# EXT-PHY.net
KiCad netlist of a schematic drawn in EAGLE
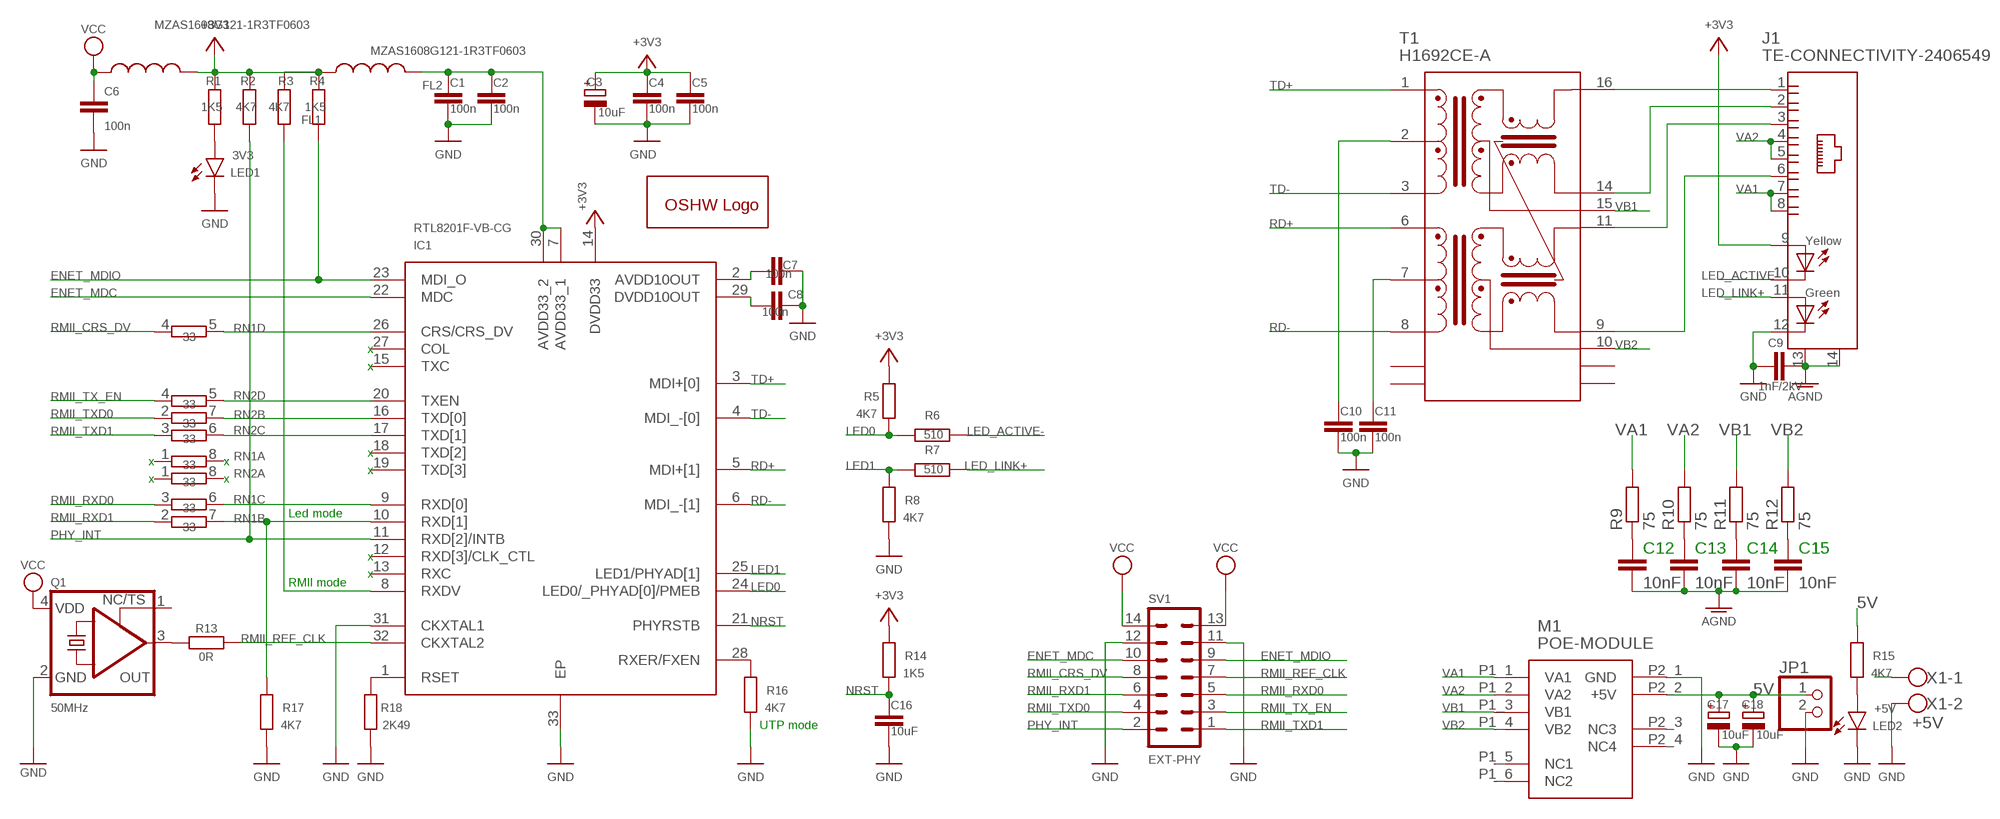
[diagram p0: schematic, sheet 1]

(export (version "E")
  (design (tool "Eeschema 10.0.6"))
  (components
    (comp (ref "C1")
      (value "100n")
      (footprint "eagle-import:C0603")
      (libsource (lib "eagle-import") (part "C-EUC0603"))
    )
    (comp (ref "C2")
      (value "100n")
      (footprint "eagle-import:C0603")
      (libsource (lib "eagle-import") (part "C-EUC0603"))
    )
    (comp (ref "C3")
      (value "10uF")
      (footprint "eagle-import:A_3216-18R")
      (libsource (lib "eagle-import") (part "CPOL-EUA/3216-18R"))
    )
    (comp (ref "C4")
      (value "100n")
      (footprint "eagle-import:C0603")
      (libsource (lib "eagle-import") (part "C-EUC0603"))
    )
    (comp (ref "C5")
      (value "100n")
      (footprint "eagle-import:C0603")
      (libsource (lib "eagle-import") (part "C-EUC0603"))
    )
    (comp (ref "C6")
      (value "100n")
      (footprint "eagle-import:C0603")
      (libsource (lib "eagle-import") (part "C-EUC0603"))
    )
    (comp (ref "C7")
      (value "100n")
      (footprint "eagle-import:C0603")
      (libsource (lib "eagle-import") (part "C-EUC0603"))
    )
    (comp (ref "C8")
      (value "100n")
      (footprint "eagle-import:C0603")
      (libsource (lib "eagle-import") (part "C-EUC0603"))
    )
    (comp (ref "C9")
      (value "1nF/2kV")
      (footprint "eagle-import:C1206")
      (fields (field (name "SPICEPREFIX") "C"))
      (libsource (lib "eagle-import") (part "C-EUC1206"))
    )
    (comp (ref "C10")
      (value "100n")
      (footprint "eagle-import:C0603")
      (libsource (lib "eagle-import") (part "C-EUC0603"))
    )
    (comp (ref "C11")
      (value "100n")
      (footprint "eagle-import:C0603")
      (libsource (lib "eagle-import") (part "C-EUC0603"))
    )
    (comp (ref "C12")
      (value "10nF")
      (footprint "eagle-import:C0805")
      (libsource (lib "eagle-import") (part "C-EUC0805"))
    )
    (comp (ref "C13")
      (value "10nF")
      (footprint "eagle-import:C0805")
      (libsource (lib "eagle-import") (part "C-EUC0805"))
    )
    (comp (ref "C14")
      (value "10nF")
      (footprint "eagle-import:C0805")
      (libsource (lib "eagle-import") (part "C-EUC0805"))
    )
    (comp (ref "C15")
      (value "10nF")
      (footprint "eagle-import:C0805")
      (libsource (lib "eagle-import") (part "C-EUC0805"))
    )
    (comp (ref "C16")
      (value "10uF")
      (footprint "eagle-import:C0603")
      (libsource (lib "eagle-import") (part "C-EUC0603"))
    )
    (comp (ref "C17")
      (value "10uF")
      (footprint "eagle-import:A_3216-18R")
      (libsource (lib "eagle-import") (part "CPOL-EUA/3216-18R"))
    )
    (comp (ref "C18")
      (value "10uF")
      (footprint "eagle-import:A_3216-18R")
      (libsource (lib "eagle-import") (part "CPOL-EUA/3216-18R"))
    )
    (comp (ref "FL1")
      (value "MZAS1608G121-1R3TF0603")
      (footprint "eagle-import:0603")
      (libsource (lib "eagle-import") (part "MZAS1608G121-1R3TF0603"))
    )
    (comp (ref "FL2")
      (value "MZAS1608G121-1R3TF0603")
      (footprint "eagle-import:0603")
      (libsource (lib "eagle-import") (part "MZAS1608G121-1R3TF0603"))
    )
    (comp (ref "GOLD_ORB_SM1")
      (value "OSHWLOGOLOGO5MM")
      (footprint "eagle-import:OSHW_5MM")
      (libsource (lib "eagle-import") (part "OSHWLOGOLOGO5MM"))
    )
    (comp (ref "IC1")
      (value "RTL8201F-VB-CG")
      (footprint "eagle-import:QFN50P500X500X100-33N")
      (fields (field (name "JLCPCB") "C45044"))
      (libsource (lib "eagle-import") (part "RTL8201F-VB-CG"))
    )
    (comp (ref "J1")
      (value "TE-CONNECTIVITY-2406549")
      (footprint "eagle-import:34065493")
      (fields (field (name "MANUFACTURER_PART_NUMBER") "2-406549-1"))
      (libsource (lib "eagle-import") (part "TE-CONNECTIVITY-2406549"))
    )
    (comp (ref "JP1")
      (value "PINHD-1X2")
      (footprint "eagle-import:1X02")
      (libsource (lib "eagle-import") (part "PINHD-1X2"))
    )
    (comp (ref "LED1")
      (value "3V3")
      (footprint "eagle-import:CHIP-LED0603")
      (libsource (lib "eagle-import") (part "LEDCHIP-LED0603"))
    )
    (comp (ref "LED2")
      (value "+5V")
      (footprint "eagle-import:CHIP-LED0603")
      (libsource (lib "eagle-import") (part "LEDCHIP-LED0603"))
    )
    (comp (ref "M1")
      (value "POE-MODULE")
      (footprint "eagle-import:POE-MODULE")
      (libsource (lib "eagle-import") (part "POE-MODULE"))
    )
    (comp (ref "Q1")
      (value "50MHz")
      (footprint "eagle-import:3.2X2.5_KXO-V96")
      (libsource (lib "eagle-import") (part "KXO-PXO/XO-V96"))
    )
    (comp (ref "R1")
      (value "1K5")
      (footprint "eagle-import:R0603")
      (libsource (lib "eagle-import") (part "R-EU_R0603"))
    )
    (comp (ref "R2")
      (value "4K7")
      (footprint "eagle-import:R0603")
      (libsource (lib "eagle-import") (part "R-EU_R0603"))
    )
    (comp (ref "R3")
      (value "4K7")
      (footprint "eagle-import:R0603")
      (libsource (lib "eagle-import") (part "R-EU_R0603"))
    )
    (comp (ref "R4")
      (value "1K5")
      (footprint "eagle-import:R0603")
      (libsource (lib "eagle-import") (part "R-EU_R0603"))
    )
    (comp (ref "R5")
      (value "4K7")
      (footprint "eagle-import:R0603")
      (libsource (lib "eagle-import") (part "R-EU_R0603"))
    )
    (comp (ref "R6")
      (value "510")
      (footprint "eagle-import:R0603")
      (libsource (lib "eagle-import") (part "R-EU_R0603"))
    )
    (comp (ref "R7")
      (value "510")
      (footprint "eagle-import:R0603")
      (libsource (lib "eagle-import") (part "R-EU_R0603"))
    )
    (comp (ref "R8")
      (value "4K7")
      (footprint "eagle-import:R0603")
      (libsource (lib "eagle-import") (part "R-EU_R0603"))
    )
    (comp (ref "R9")
      (value "75")
      (footprint "eagle-import:R0603")
      (libsource (lib "eagle-import") (part "R-EU_R0603"))
    )
    (comp (ref "R10")
      (value "75")
      (footprint "eagle-import:R0603")
      (libsource (lib "eagle-import") (part "R-EU_R0603"))
    )
    (comp (ref "R11")
      (value "75")
      (footprint "eagle-import:R0603")
      (libsource (lib "eagle-import") (part "R-EU_R0603"))
    )
    (comp (ref "R12")
      (value "75")
      (footprint "eagle-import:R0603")
      (libsource (lib "eagle-import") (part "R-EU_R0603"))
    )
    (comp (ref "R13")
      (value "0R")
      (footprint "eagle-import:R0603")
      (libsource (lib "eagle-import") (part "R-EU_R0603"))
    )
    (comp (ref "R14")
      (value "1K5")
      (footprint "eagle-import:R0603")
      (libsource (lib "eagle-import") (part "R-EU_R0603"))
    )
    (comp (ref "R15")
      (value "4K7")
      (footprint "eagle-import:R0603")
      (libsource (lib "eagle-import") (part "R-EU_R0603"))
    )
    (comp (ref "R16")
      (value "4K7")
      (footprint "eagle-import:R0603")
      (libsource (lib "eagle-import") (part "R-EU_R0603"))
    )
    (comp (ref "R17")
      (value "4K7")
      (footprint "eagle-import:R0603")
      (libsource (lib "eagle-import") (part "R-EU_R0603"))
    )
    (comp (ref "R18")
      (value "2K49")
      (footprint "eagle-import:R0603")
      (libsource (lib "eagle-import") (part "R-EU_R0603"))
    )
    (comp (ref "RN1")
      (value "33")
      (footprint "eagle-import:4X0402ARV341")
      (fields (field (name "JLCPCB") "C25501"))
      (libsource (lib "eagle-import") (part "4R-N0402ARV341"))
    )
    (comp (ref "RN2")
      (value "33")
      (footprint "eagle-import:4X0402ARV341")
      (fields (field (name "JLCPCB") "C25501"))
      (libsource (lib "eagle-import") (part "4R-N0402ARV341"))
    )
    (comp (ref "SV1")
      (value "EXT-PHY")
      (footprint "eagle-import:MA07-2W")
      (libsource (lib "eagle-import") (part "MA07-2W"))
    )
    (comp (ref "T1")
      (value "H1692CE-A")
      (footprint "eagle-import:SOIC127P952X572-16N")
      (fields (field (name "MANUFACTURER") "Dongguan Mentech Optical & Magnetic"))
      (libsource (lib "eagle-import") (part "H1692CE-A"))
    )
    (comp (ref "X1")
      (value "+5V")
      (footprint "eagle-import:W237-102")
      (fields (field (name "MPN") "237-102"))
      (libsource (lib "eagle-import") (part "W237-102"))
    )
  )
  (nets
    (net (code "1") (name "+3V3") (class "Default")
      (node (ref "C3") (pin "+") (pinfunction "+_+") (pintype "passive"))
      (node (ref "C4") (pin "1") (pinfunction "1_1") (pintype "passive"))
      (node (ref "C5") (pin "1") (pinfunction "1_1") (pintype "passive"))
      (node (ref "FL1") (pin "2") (pinfunction "2_2") (pintype "passive"))
      (node (ref "FL2") (pin "1") (pinfunction "1_1") (pintype "passive"))
      (node (ref "IC1") (pin "14") (pinfunction "DVDD33_14") (pintype "bidirectional"))
      (node (ref "J1") (pin "9") (pinfunction "+_1_9") (pintype "bidirectional"))
      (node (ref "R1") (pin "2") (pinfunction "2_2") (pintype "passive"))
      (node (ref "R14") (pin "2") (pinfunction "2_2") (pintype "passive"))
      (node (ref "R2") (pin "2") (pinfunction "2_2") (pintype "passive"))
      (node (ref "R3") (pin "1") (pinfunction "1_1") (pintype "passive"))
      (node (ref "R4") (pin "2") (pinfunction "2_2") (pintype "passive"))
      (node (ref "R5") (pin "2") (pinfunction "2_2") (pintype "passive"))
    )
    (net (code "2") (name "/5V") (class "Default")
      (node (ref "C17") (pin "+") (pinfunction "+_+") (pintype "passive"))
      (node (ref "C18") (pin "+") (pinfunction "+_+") (pintype "passive"))
      (node (ref "JP1") (pin "1") (pinfunction "1_1") (pintype "passive"))
      (node (ref "M1") (pin "P2_2") (pinfunction "+5V_P2_2") (pintype "power_in"))
      (node (ref "R15") (pin "2") (pinfunction "2_2") (pintype "passive"))
      (node (ref "X1") (pin "1") (pinfunction "KL_1") (pintype "passive"))
    )
    (net (code "3") (name "/ENET_MDC") (class "Default")
      (node (ref "IC1") (pin "22") (pinfunction "MDC_22") (pintype "bidirectional"))
      (node (ref "SV1") (pin "10") (pinfunction "10_10") (pintype "passive"))
    )
    (net (code "4") (name "/ENET_MDIO") (class "Default")
      (node (ref "IC1") (pin "23") (pinfunction "MDI_O_23") (pintype "bidirectional"))
      (node (ref "R4") (pin "1") (pinfunction "1_1") (pintype "passive"))
      (node (ref "SV1") (pin "9") (pinfunction "9_9") (pintype "passive"))
    )
    (net (code "5") (name "/LED0") (class "Default")
      (node (ref "IC1") (pin "24") (pinfunction "LED0/_PHYAD[0]/PMEB_24") (pintype "bidirectional"))
      (node (ref "R5") (pin "1") (pinfunction "1_1") (pintype "passive"))
      (node (ref "R6") (pin "2") (pinfunction "2_2") (pintype "passive"))
    )
    (net (code "6") (name "/LED1") (class "Default")
      (node (ref "IC1") (pin "25") (pinfunction "LED1/PHYAD[1]_25") (pintype "bidirectional"))
      (node (ref "R7") (pin "2") (pinfunction "2_2") (pintype "passive"))
      (node (ref "R8") (pin "2") (pinfunction "2_2") (pintype "passive"))
    )
    (net (code "7") (name "/LED_ACTIVE-") (class "Default")
      (node (ref "J1") (pin "10") (pinfunction "-_1_10") (pintype "bidirectional"))
      (node (ref "R6") (pin "1") (pinfunction "1_1") (pintype "passive"))
    )
    (net (code "8") (name "/LED_LINK+") (class "Default")
      (node (ref "J1") (pin "11") (pinfunction "+_2_11") (pintype "bidirectional"))
      (node (ref "R7") (pin "1") (pinfunction "1_1") (pintype "passive"))
    )
    (net (code "9") (name "/NRST") (class "Default")
      (node (ref "C16") (pin "1") (pinfunction "1_1") (pintype "passive"))
      (node (ref "IC1") (pin "21") (pinfunction "PHYRSTB_21") (pintype "bidirectional"))
      (node (ref "R14") (pin "1") (pinfunction "1_1") (pintype "passive"))
    )
    (net (code "10") (name "/PHY_INT") (class "Default")
      (node (ref "IC1") (pin "11") (pinfunction "RXD[2]/INTB_11") (pintype "bidirectional"))
      (node (ref "R2") (pin "1") (pinfunction "1_1") (pintype "passive"))
      (node (ref "SV1") (pin "2") (pinfunction "2_2") (pintype "passive"))
    )
    (net (code "11") (name "/RD+") (class "Default")
      (node (ref "IC1") (pin "5") (pinfunction "MDI+[1]_5") (pintype "bidirectional"))
      (node (ref "T1") (pin "6") (pinfunction "6_6") (pintype "passive"))
    )
    (net (code "12") (name "/RD-") (class "Default")
      (node (ref "IC1") (pin "6") (pinfunction "MDI_-[1]_6") (pintype "bidirectional"))
      (node (ref "T1") (pin "8") (pinfunction "8_8") (pintype "passive"))
    )
    (net (code "13") (name "/RMII_CRS_DV") (class "Default")
      (node (ref "RN1") (pin "4") (pinfunction "1_4") (pintype "passive"))
      (node (ref "SV1") (pin "8") (pinfunction "8_8") (pintype "passive"))
    )
    (net (code "14") (name "/RMII_REF_CLK") (class "Default")
      (node (ref "IC1") (pin "32") (pinfunction "CKXTAL2_32") (pintype "bidirectional"))
      (node (ref "R13") (pin "2") (pinfunction "2_2") (pintype "passive"))
      (node (ref "SV1") (pin "7") (pinfunction "7_7") (pintype "passive"))
    )
    (net (code "15") (name "/RMII_RXD0") (class "Default")
      (node (ref "RN1") (pin "3") (pinfunction "1_3") (pintype "passive"))
      (node (ref "SV1") (pin "5") (pinfunction "5_5") (pintype "passive"))
    )
    (net (code "16") (name "/RMII_RXD1") (class "Default")
      (node (ref "RN1") (pin "2") (pinfunction "1_2") (pintype "passive"))
      (node (ref "SV1") (pin "6") (pinfunction "6_6") (pintype "passive"))
    )
    (net (code "17") (name "/RMII_TXD0") (class "Default")
      (node (ref "RN2") (pin "2") (pinfunction "1_2") (pintype "passive"))
      (node (ref "SV1") (pin "4") (pinfunction "4_4") (pintype "passive"))
    )
    (net (code "18") (name "/RMII_TXD1") (class "Default")
      (node (ref "RN2") (pin "3") (pinfunction "1_3") (pintype "passive"))
      (node (ref "SV1") (pin "1") (pinfunction "1_1") (pintype "passive"))
    )
    (net (code "19") (name "/RMII_TX_EN") (class "Default")
      (node (ref "RN2") (pin "4") (pinfunction "1_4") (pintype "passive"))
      (node (ref "SV1") (pin "3") (pinfunction "3_3") (pintype "passive"))
    )
    (net (code "20") (name "/TD+") (class "Default")
      (node (ref "IC1") (pin "3") (pinfunction "MDI+[0]_3") (pintype "bidirectional"))
      (node (ref "T1") (pin "1") (pinfunction "1_1") (pintype "passive"))
    )
    (net (code "21") (name "/TD-") (class "Default")
      (node (ref "IC1") (pin "4") (pinfunction "MDI_-[0]_4") (pintype "bidirectional"))
      (node (ref "T1") (pin "3") (pinfunction "3_3") (pintype "passive"))
    )
    (net (code "22") (name "/VA1") (class "Default")
      (node (ref "J1") (pin "7") (pinfunction "7_7") (pintype "passive"))
      (node (ref "J1") (pin "8") (pinfunction "8_8") (pintype "passive"))
      (node (ref "M1") (pin "P1_1") (pinfunction "VA1_P1_1") (pintype "power_in"))
      (node (ref "R9") (pin "2") (pinfunction "2_2") (pintype "passive"))
    )
    (net (code "23") (name "/VA2") (class "Default")
      (node (ref "J1") (pin "4") (pinfunction "4_4") (pintype "passive"))
      (node (ref "J1") (pin "5") (pinfunction "5_5") (pintype "passive"))
      (node (ref "M1") (pin "P1_2") (pinfunction "VA2_P1_2") (pintype "power_in"))
      (node (ref "R10") (pin "2") (pinfunction "2_2") (pintype "passive"))
    )
    (net (code "24") (name "/VB1") (class "Default")
      (node (ref "M1") (pin "P1_3") (pinfunction "VB1_P1_3") (pintype "power_in"))
      (node (ref "R11") (pin "2") (pinfunction "2_2") (pintype "passive"))
      (node (ref "T1") (pin "15") (pinfunction "15_15") (pintype "passive"))
    )
    (net (code "25") (name "/VB2") (class "Default")
      (node (ref "M1") (pin "P1_4") (pinfunction "VB2_P1_4") (pintype "power_in"))
      (node (ref "R12") (pin "2") (pinfunction "2_2") (pintype "passive"))
      (node (ref "T1") (pin "10") (pinfunction "10_10") (pintype "passive"))
    )
    (net (code "26") (name "AGND") (class "Default")
      (node (ref "C12") (pin "2") (pinfunction "2_2") (pintype "passive"))
      (node (ref "C13") (pin "2") (pinfunction "2_2") (pintype "passive"))
      (node (ref "C14") (pin "2") (pinfunction "2_2") (pintype "passive"))
      (node (ref "C15") (pin "2") (pinfunction "2_2") (pintype "passive"))
      (node (ref "C9") (pin "2") (pinfunction "2_2") (pintype "passive"))
      (node (ref "J1") (pin "13") (pinfunction "S1_13") (pintype "passive"))
      (node (ref "J1") (pin "14") (pinfunction "S2_14") (pintype "passive"))
    )
    (net (code "27") (name "GND") (class "Default")
      (node (ref "C1") (pin "2") (pinfunction "2_2") (pintype "passive"))
      (node (ref "C10") (pin "2") (pinfunction "2_2") (pintype "passive"))
      (node (ref "C11") (pin "2") (pinfunction "2_2") (pintype "passive"))
      (node (ref "C16") (pin "2") (pinfunction "2_2") (pintype "passive"))
      (node (ref "C17") (pin "-") (pinfunction "-_-") (pintype "passive"))
      (node (ref "C18") (pin "-") (pinfunction "-_-") (pintype "passive"))
      (node (ref "C2") (pin "2") (pinfunction "2_2") (pintype "passive"))
      (node (ref "C3") (pin "-") (pinfunction "-_-") (pintype "passive"))
      (node (ref "C4") (pin "2") (pinfunction "2_2") (pintype "passive"))
      (node (ref "C5") (pin "2") (pinfunction "2_2") (pintype "passive"))
      (node (ref "C6") (pin "2") (pinfunction "2_2") (pintype "passive"))
      (node (ref "C7") (pin "2") (pinfunction "2_2") (pintype "passive"))
      (node (ref "C8") (pin "1") (pinfunction "1_1") (pintype "passive"))
      (node (ref "C9") (pin "1") (pinfunction "1_1") (pintype "passive"))
      (node (ref "IC1") (pin "31") (pinfunction "CKXTAL1_31") (pintype "bidirectional"))
      (node (ref "IC1") (pin "33") (pinfunction "EP_33") (pintype "bidirectional"))
      (node (ref "J1") (pin "12") (pinfunction "-_2_12") (pintype "bidirectional"))
      (node (ref "JP1") (pin "2") (pinfunction "2_2") (pintype "passive"))
      (node (ref "LED1") (pin "C") (pinfunction "C_C") (pintype "passive"))
      (node (ref "LED2") (pin "C") (pinfunction "C_C") (pintype "passive"))
      (node (ref "M1") (pin "P2_1") (pinfunction "GND_P2_1") (pintype "power_in"))
      (node (ref "Q1") (pin "2") (pinfunction "GND_2") (pintype "power_in"))
      (node (ref "R16") (pin "1") (pinfunction "1_1") (pintype "passive"))
      (node (ref "R17") (pin "1") (pinfunction "1_1") (pintype "passive"))
      (node (ref "R18") (pin "2") (pinfunction "2_2") (pintype "passive"))
      (node (ref "R8") (pin "1") (pinfunction "1_1") (pintype "passive"))
      (node (ref "SV1") (pin "11") (pinfunction "11_11") (pintype "passive"))
      (node (ref "SV1") (pin "12") (pinfunction "12_12") (pintype "passive"))
      (node (ref "X1") (pin "2") (pinfunction "KL_2") (pintype "passive"))
    )
    (net (code "28") (name "Net-(C10-Pad1)") (class "Default")
      (node (ref "C10") (pin "1") (pinfunction "1_1") (pintype "passive"))
      (node (ref "T1") (pin "2") (pinfunction "2_2") (pintype "passive"))
    )
    (net (code "29") (name "Net-(C11-Pad1)") (class "Default")
      (node (ref "C11") (pin "1") (pinfunction "1_1") (pintype "passive"))
      (node (ref "T1") (pin "7") (pinfunction "7_7") (pintype "passive"))
    )
    (net (code "30") (name "Net-(C12-Pad1)") (class "Default")
      (node (ref "C12") (pin "1") (pinfunction "1_1") (pintype "passive"))
      (node (ref "R9") (pin "1") (pinfunction "1_1") (pintype "passive"))
    )
    (net (code "31") (name "Net-(C13-Pad1)") (class "Default")
      (node (ref "C13") (pin "1") (pinfunction "1_1") (pintype "passive"))
      (node (ref "R10") (pin "1") (pinfunction "1_1") (pintype "passive"))
    )
    (net (code "32") (name "Net-(C14-Pad1)") (class "Default")
      (node (ref "C14") (pin "1") (pinfunction "1_1") (pintype "passive"))
      (node (ref "R11") (pin "1") (pinfunction "1_1") (pintype "passive"))
    )
    (net (code "33") (name "Net-(C15-Pad1)") (class "Default")
      (node (ref "C15") (pin "1") (pinfunction "1_1") (pintype "passive"))
      (node (ref "R12") (pin "1") (pinfunction "1_1") (pintype "passive"))
    )
    (net (code "34") (name "Net-(IC1-AVDD10OUT)") (class "Default")
      (node (ref "C7") (pin "1") (pinfunction "1_1") (pintype "passive"))
      (node (ref "IC1") (pin "2") (pinfunction "AVDD10OUT_2") (pintype "bidirectional"))
    )
    (net (code "35") (name "Net-(IC1-AVDD33_1)") (class "Default")
      (node (ref "C1") (pin "1") (pinfunction "1_1") (pintype "passive"))
      (node (ref "C2") (pin "1") (pinfunction "1_1") (pintype "passive"))
      (node (ref "FL2") (pin "2") (pinfunction "2_2") (pintype "passive"))
      (node (ref "IC1") (pin "30") (pinfunction "AVDD33_2_30") (pintype "bidirectional"))
      (node (ref "IC1") (pin "7") (pinfunction "AVDD33_1_7") (pintype "bidirectional"))
    )
    (net (code "36") (name "Net-(IC1-CRS{slash}CRS_DV)") (class "Default")
      (node (ref "IC1") (pin "26") (pinfunction "CRS/CRS_DV_26") (pintype "bidirectional"))
      (node (ref "RN1") (pin "5") (pinfunction "2_5") (pintype "passive"))
    )
    (net (code "37") (name "Net-(IC1-DVDD10OUT)") (class "Default")
      (node (ref "C8") (pin "2") (pinfunction "2_2") (pintype "passive"))
      (node (ref "IC1") (pin "29") (pinfunction "DVDD10OUT_29") (pintype "bidirectional"))
    )
    (net (code "38") (name "Net-(IC1-RSET)") (class "Default")
      (node (ref "IC1") (pin "1") (pinfunction "RSET_1") (pintype "bidirectional"))
      (node (ref "R18") (pin "1") (pinfunction "1_1") (pintype "passive"))
    )
    (net (code "39") (name "Net-(IC1-RXDV)") (class "Default")
      (node (ref "IC1") (pin "8") (pinfunction "RXDV_8") (pintype "bidirectional"))
      (node (ref "R3") (pin "2") (pinfunction "2_2") (pintype "passive"))
    )
    (net (code "40") (name "Net-(IC1-RXD[0])") (class "Default")
      (node (ref "IC1") (pin "9") (pinfunction "RXD[0]_9") (pintype "bidirectional"))
      (node (ref "RN1") (pin "6") (pinfunction "2_6") (pintype "passive"))
    )
    (net (code "41") (name "Net-(IC1-RXD[1])") (class "Default")
      (node (ref "IC1") (pin "10") (pinfunction "RXD[1]_10") (pintype "bidirectional"))
      (node (ref "R17") (pin "2") (pinfunction "2_2") (pintype "passive"))
      (node (ref "RN1") (pin "7") (pinfunction "2_7") (pintype "passive"))
    )
    (net (code "42") (name "Net-(IC1-RXER{slash}FXEN)") (class "Default")
      (node (ref "IC1") (pin "28") (pinfunction "RXER/FXEN_28") (pintype "bidirectional"))
      (node (ref "R16") (pin "2") (pinfunction "2_2") (pintype "passive"))
    )
    (net (code "43") (name "Net-(IC1-TXD[0])") (class "Default")
      (node (ref "IC1") (pin "16") (pinfunction "TXD[0]_16") (pintype "bidirectional"))
      (node (ref "RN2") (pin "7") (pinfunction "2_7") (pintype "passive"))
    )
    (net (code "44") (name "Net-(IC1-TXD[1])") (class "Default")
      (node (ref "IC1") (pin "17") (pinfunction "TXD[1]_17") (pintype "bidirectional"))
      (node (ref "RN2") (pin "6") (pinfunction "2_6") (pintype "passive"))
    )
    (net (code "45") (name "Net-(IC1-TXEN)") (class "Default")
      (node (ref "IC1") (pin "20") (pinfunction "TXEN_20") (pintype "bidirectional"))
      (node (ref "RN2") (pin "5") (pinfunction "2_5") (pintype "passive"))
    )
    (net (code "46") (name "Net-(J1-Pad1)") (class "Default")
      (node (ref "J1") (pin "1") (pinfunction "1_1") (pintype "passive"))
      (node (ref "T1") (pin "16") (pinfunction "16_16") (pintype "passive"))
    )
    (net (code "47") (name "Net-(J1-Pad2)") (class "Default")
      (node (ref "J1") (pin "2") (pinfunction "2_2") (pintype "passive"))
      (node (ref "T1") (pin "14") (pinfunction "14_14") (pintype "passive"))
    )
    (net (code "48") (name "Net-(J1-Pad3)") (class "Default")
      (node (ref "J1") (pin "3") (pinfunction "3_3") (pintype "passive"))
      (node (ref "T1") (pin "11") (pinfunction "11_11") (pintype "passive"))
    )
    (net (code "49") (name "Net-(J1-Pad6)") (class "Default")
      (node (ref "J1") (pin "6") (pinfunction "6_6") (pintype "passive"))
      (node (ref "T1") (pin "9") (pinfunction "9_9") (pintype "passive"))
    )
    (net (code "50") (name "Net-(LED1-PadA)") (class "Default")
      (node (ref "LED1") (pin "A") (pinfunction "A_A") (pintype "passive"))
      (node (ref "R1") (pin "1") (pinfunction "1_1") (pintype "passive"))
    )
    (net (code "51") (name "Net-(LED2-PadA)") (class "Default")
      (node (ref "LED2") (pin "A") (pinfunction "A_A") (pintype "passive"))
      (node (ref "R15") (pin "1") (pinfunction "1_1") (pintype "passive"))
    )
    (net (code "52") (name "Net-(Q1-OUT)") (class "Default")
      (node (ref "Q1") (pin "3") (pinfunction "OUT_3") (pintype "output"))
      (node (ref "R13") (pin "1") (pinfunction "1_1") (pintype "passive"))
    )
    (net (code "53") (name "VCC") (class "Default")
      (node (ref "C6") (pin "1") (pinfunction "1_1") (pintype "passive"))
      (node (ref "FL1") (pin "1") (pinfunction "1_1") (pintype "passive"))
      (node (ref "Q1") (pin "4") (pinfunction "VDD_4") (pintype "power_in"))
      (node (ref "SV1") (pin "13") (pinfunction "13_13") (pintype "passive"))
      (node (ref "SV1") (pin "14") (pinfunction "14_14") (pintype "passive"))
    )
    (net (code "54") (name "unconnected-(IC1-COL-Pad27)") (class "Default")
      (node (ref "IC1") (pin "27") (pinfunction "COL_27") (pintype "bidirectional"))
    )
    (net (code "55") (name "unconnected-(IC1-RXC-Pad13)") (class "Default")
      (node (ref "IC1") (pin "13") (pinfunction "RXC_13") (pintype "bidirectional"))
    )
    (net (code "56") (name "unconnected-(IC1-RXD[3]{slash}CLK_CTL-Pad12)") (class "Default")
      (node (ref "IC1") (pin "12") (pinfunction "RXD[3]/CLK_CTL_12") (pintype "bidirectional"))
    )
    (net (code "57") (name "unconnected-(IC1-TXC-Pad15)") (class "Default")
      (node (ref "IC1") (pin "15") (pinfunction "TXC_15") (pintype "bidirectional"))
    )
    (net (code "58") (name "unconnected-(IC1-TXD[2]-Pad18)") (class "Default")
      (node (ref "IC1") (pin "18") (pinfunction "TXD[2]_18") (pintype "bidirectional"))
    )
    (net (code "59") (name "unconnected-(IC1-TXD[3]-Pad19)") (class "Default")
      (node (ref "IC1") (pin "19") (pinfunction "TXD[3]_19") (pintype "bidirectional"))
    )
    (net (code "60") (name "unconnected-(M1-NC1-PadP1_5)") (class "Default")
      (node (ref "M1") (pin "P1_5") (pinfunction "NC1_P1_5") (pintype "no_connect"))
    )
    (net (code "61") (name "unconnected-(M1-NC2-PadP1_6)") (class "Default")
      (node (ref "M1") (pin "P1_6") (pinfunction "NC2_P1_6") (pintype "no_connect"))
    )
    (net (code "62") (name "unconnected-(M1-NC3-PadP2_3)") (class "Default")
      (node (ref "M1") (pin "P2_3") (pinfunction "NC3_P2_3") (pintype "no_connect"))
    )
    (net (code "63") (name "unconnected-(M1-NC4-PadP2_4)") (class "Default")
      (node (ref "M1") (pin "P2_4") (pinfunction "NC4_P2_4") (pintype "no_connect"))
    )
    (net (code "64") (name "unconnected-(Q1-TS-Pad1)") (class "Default")
      (node (ref "Q1") (pin "1") (pinfunction "TS_1") (pintype "passive"))
    )
    (net (code "65") (name "unconnected-(RN1-Pad1)") (class "Default")
      (node (ref "RN1") (pin "1") (pinfunction "1_1") (pintype "passive"))
    )
    (net (code "66") (name "unconnected-(RN1A-2-Pad8)") (class "Default")
      (node (ref "RN1") (pin "8") (pinfunction "2_8") (pintype "passive"))
    )
    (net (code "67") (name "unconnected-(RN2-Pad1)") (class "Default")
      (node (ref "RN2") (pin "1") (pinfunction "1_1") (pintype "passive"))
    )
    (net (code "68") (name "unconnected-(RN2A-2-Pad8)") (class "Default")
      (node (ref "RN2") (pin "8") (pinfunction "2_8") (pintype "passive"))
    )
    (net (code "69") (name "unconnected-(T1-Pad4)") (class "Default")
      (node (ref "T1") (pin "4") (pinfunction "4_4") (pintype "no_connect"))
    )
    (net (code "70") (name "unconnected-(T1-Pad5)") (class "Default")
      (node (ref "T1") (pin "5") (pinfunction "5_5") (pintype "no_connect"))
    )
    (net (code "71") (name "unconnected-(T1-Pad12)") (class "Default")
      (node (ref "T1") (pin "12") (pinfunction "12_12") (pintype "no_connect"))
    )
    (net (code "72") (name "unconnected-(T1-Pad13)") (class "Default")
      (node (ref "T1") (pin "13") (pinfunction "13_13") (pintype "no_connect"))
    )
  )
)
